# GPS.net
KiCad netlist of a schematic drawn in Altium Designer
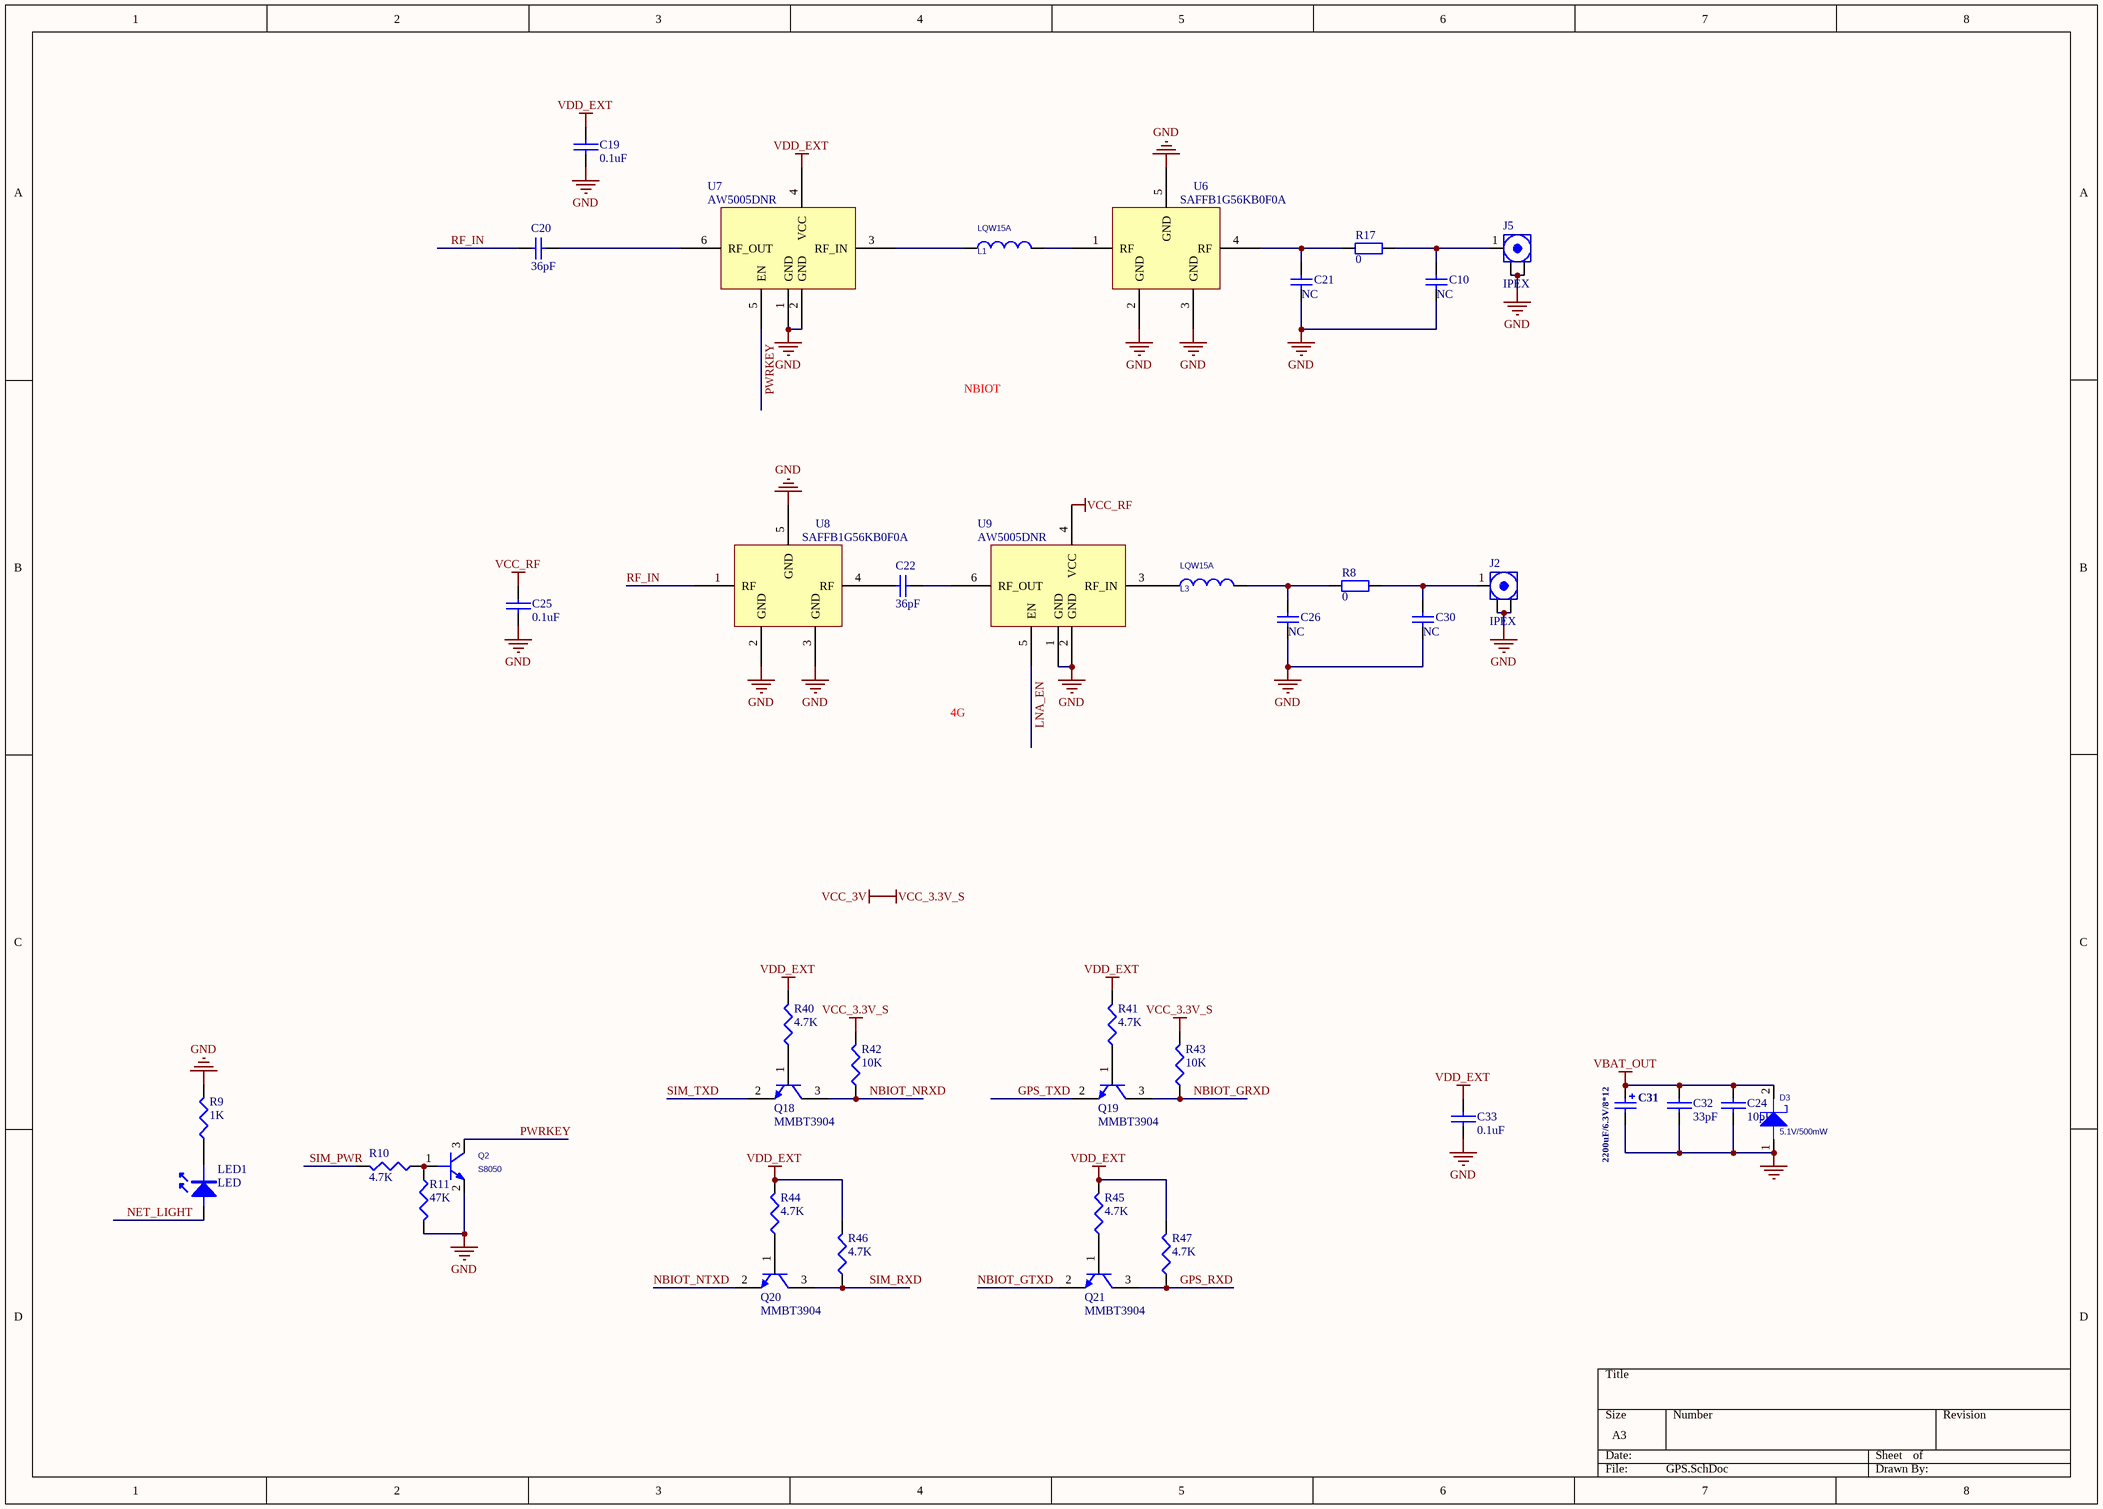
[diagram p0: GPS.SchDoc]

(export (version "E")
  (design (tool "Eeschema 10.0.6"))
  (components
    (comp (ref "C10")
      (value "NC")
      (footprint "0603C")
      (description "Capacitor")
      (fields (field (name "PUBLISHER") "Altium Limited"))
      (libsource (lib "Miscellaneous Devices") (part "Cap"))
    )
    (comp (ref "C19")
      (value "0.1uF")
      (footprint "0603C")
      (description "Capacitor")
      (libsource (lib "ZWLIntegrated_Library") (part "CAP"))
    )
    (comp (ref "C20")
      (value "36pF")
      (footprint "0603C")
      (description "Capacitor")
      (fields (field (name "PUBLISHER") "Altium Limited"))
      (libsource (lib "Miscellaneous Devices") (part "Cap"))
    )
    (comp (ref "C21")
      (value "NC")
      (footprint "0603C")
      (description "Capacitor")
      (fields (field (name "PUBLISHER") "Altium Limited"))
      (libsource (lib "Miscellaneous Devices") (part "Cap"))
    )
    (comp (ref "C22")
      (value "36pF")
      (footprint "0603C")
      (description "Capacitor")
      (fields (field (name "PUBLISHER") "Altium Limited"))
      (libsource (lib "Miscellaneous Devices") (part "Cap"))
    )
    (comp (ref "C24")
      (value "10pF")
      (footprint "0603C")
      (description "Capacitor")
      (libsource (lib "ZWLIntegrated_Library") (part "CAP"))
    )
    (comp (ref "C25")
      (value "0.1uF")
      (footprint "0603C")
      (description "Capacitor")
      (libsource (lib "ZWLIntegrated_Library") (part "CAP"))
    )
    (comp (ref "C26")
      (value "NC")
      (footprint "0603C")
      (description "Capacitor")
      (fields (field (name "PUBLISHER") "Altium Limited"))
      (libsource (lib "Miscellaneous Devices") (part "Cap"))
    )
    (comp (ref "C30")
      (value "NC")
      (footprint "0603C")
      (description "Capacitor")
      (fields (field (name "PUBLISHER") "Altium Limited"))
      (libsource (lib "Miscellaneous Devices") (part "Cap"))
    )
    (comp (ref "C31")
      (value "2200uF/6.3V/8*12")
      (footprint "8*12")
      (description "Polarized Capacitor (Surface Mount)")
      (libsource (lib "KT_iBeacon") (part "Cap Pol3"))
    )
    (comp (ref "C32")
      (value "33pF")
      (footprint "0603C")
      (description "Capacitor")
      (libsource (lib "ZWLIntegrated_Library") (part "CAP"))
    )
    (comp (ref "C33")
      (value "0.1uF")
      (footprint "0603C")
      (description "Capacitor")
      (libsource (lib "ZWLIntegrated_Library") (part "CAP"))
    )
    (comp (ref "D3")
      (value "5.1V/500mW")
      (footprint "LL-34(D1206)")
      (fields (field (name "Comment") "DIODE_SCHOTTKY_0"))
      (libsource (lib "KT_iBeacon") (part "DIODE_SCHOTTKY_0"))
    )
    (comp (ref "J2") (value "IPEX") (footprint "RF-UFL") (libsource (lib "我的元件库") (part "ANT")))
    (comp (ref "J5") (value "IPEX") (footprint "RF-UFL") (libsource (lib "我的元件库") (part "ANT")))
    (comp (ref "L1") (value "LQW15A") (footprint "0402R") (libsource (lib "*") (part "INDUCTOR_1")))
    (comp (ref "L3") (value "LQW15A") (footprint "0402R") (libsource (lib "*") (part "INDUCTOR_1")))
    (comp (ref "LED1") (value "LED") (footprint "0603LED") (libsource (lib "我的元件库") (part "LED")))
    (comp (ref "Q2") (value "S8050") (footprint "SOT23") (libsource (lib "*") (part "2N1069_1")))
    (comp (ref "Q18") (value "MMBT3904") (footprint "SOT23-3") (libsource (lib "Schlib1") (part "NPN")))
    (comp (ref "Q19") (value "MMBT3904") (footprint "SOT23-3") (libsource (lib "Schlib1") (part "NPN")))
    (comp (ref "Q20") (value "MMBT3904") (footprint "SOT23-3") (libsource (lib "Schlib1") (part "NPN")))
    (comp (ref "Q21") (value "MMBT3904") (footprint "SOT23-3") (libsource (lib "Schlib1") (part "NPN")))
    (comp (ref "R8")
      (value "0")
      (footprint "0603R")
      (description "Resistor")
      (fields (field (name "PUBLISHER") "Altium Limited"))
      (libsource (lib "Miscellaneous Devices") (part "Res2"))
    )
    (comp (ref "R9") (value "1K") (footprint "0603R") (libsource (lib "ZWLIntegrated_Library") (part "RES1")))
    (comp (ref "R10")
      (value "4.7K")
      (footprint "0603R")
      (libsource (lib "ZWLIntegrated_Library") (part "RES1"))
    )
    (comp (ref "R11")
      (value "47K")
      (footprint "0603R")
      (libsource (lib "ZWLIntegrated_Library") (part "RES1"))
    )
    (comp (ref "R17")
      (value "0")
      (footprint "0603R")
      (description "Resistor")
      (fields (field (name "PUBLISHER") "Altium Limited"))
      (libsource (lib "Miscellaneous Devices") (part "Res2"))
    )
    (comp (ref "R40")
      (value "4.7K")
      (footprint "0603R")
      (libsource (lib "ZWLIntegrated_Library") (part "RES1"))
    )
    (comp (ref "R41")
      (value "4.7K")
      (footprint "0603R")
      (libsource (lib "ZWLIntegrated_Library") (part "RES1"))
    )
    (comp (ref "R42")
      (value "10K")
      (footprint "0603R")
      (libsource (lib "ZWLIntegrated_Library") (part "RES1"))
    )
    (comp (ref "R43")
      (value "10K")
      (footprint "0603R")
      (libsource (lib "ZWLIntegrated_Library") (part "RES1"))
    )
    (comp (ref "R44")
      (value "4.7K")
      (footprint "0603R")
      (libsource (lib "ZWLIntegrated_Library") (part "RES1"))
    )
    (comp (ref "R45")
      (value "4.7K")
      (footprint "0603R")
      (libsource (lib "ZWLIntegrated_Library") (part "RES1"))
    )
    (comp (ref "R46")
      (value "4.7K")
      (footprint "0603R")
      (libsource (lib "ZWLIntegrated_Library") (part "RES1"))
    )
    (comp (ref "R47")
      (value "4.7K")
      (footprint "0603R")
      (libsource (lib "ZWLIntegrated_Library") (part "RES1"))
    )
    (comp (ref "U6")
      (value "SAFFB1G56KB0F0A")
      (footprint "SAFFB1G56KB0F0A")
      (libsource (lib "stm32") (part "SAFFB1G56KBOFA"))
    )
    (comp (ref "U7") (value "AW5005DNR") (libsource (lib "stm32") (part "AW5005DNR")))
    (comp (ref "U8")
      (value "SAFFB1G56KB0F0A")
      (footprint "SAFFB1G56KB0F0A")
      (libsource (lib "stm32") (part "SAFFB1G56KBOFA"))
    )
    (comp (ref "U9") (value "AW5005DNR") (libsource (lib "stm32") (part "AW5005DNR")))
  )
  (nets
    (net (code "1") (name "/GPS_RXD") (class "Default")
      (node (ref "Q21") (pin "3") (pinfunction "C_3") (pintype "passive"))
      (node (ref "R47") (pin "1") (pinfunction "1_1") (pintype "passive"))
    )
    (net (code "2") (name "/GPS_TXD") (class "Default")
      (node (ref "Q19") (pin "2") (pinfunction "E_2") (pintype "passive"))
    )
    (net (code "3") (name "/LNA_EN") (class "Default")
      (node (ref "U9") (pin "5") (pinfunction "EN_5") (pintype "passive"))
    )
    (net (code "4") (name "/NBIOT_GRXD") (class "Default")
      (node (ref "Q19") (pin "3") (pinfunction "C_3") (pintype "passive"))
      (node (ref "R43") (pin "1") (pinfunction "1_1") (pintype "passive"))
    )
    (net (code "5") (name "/NBIOT_GTXD") (class "Default")
      (node (ref "Q21") (pin "2") (pinfunction "E_2") (pintype "passive"))
    )
    (net (code "6") (name "/NBIOT_NRXD") (class "Default")
      (node (ref "Q18") (pin "3") (pinfunction "C_3") (pintype "passive"))
      (node (ref "R42") (pin "1") (pinfunction "1_1") (pintype "passive"))
    )
    (net (code "7") (name "/NBIOT_NTXD") (class "Default")
      (node (ref "Q20") (pin "2") (pinfunction "E_2") (pintype "passive"))
    )
    (net (code "8") (name "/NET_LIGHT") (class "Default")
      (node (ref "LED1") (pin "1") (pinfunction "1_1") (pintype "passive"))
    )
    (net (code "9") (name "/PWRKEY") (class "Default")
      (node (ref "Q2") (pin "3") (pinfunction "C_3") (pintype "passive"))
      (node (ref "U7") (pin "5") (pinfunction "EN_5") (pintype "passive"))
    )
    (net (code "10") (name "/RF_IN") (class "Default")
      (node (ref "C20") (pin "1") (pinfunction "1_1") (pintype "passive"))
      (node (ref "U8") (pin "1") (pinfunction "RF_1") (pintype "passive"))
    )
    (net (code "11") (name "/SIM_PWR") (class "Default")
      (node (ref "R10") (pin "2") (pinfunction "2_2") (pintype "passive"))
    )
    (net (code "12") (name "/SIM_RXD") (class "Default")
      (node (ref "Q20") (pin "3") (pinfunction "C_3") (pintype "passive"))
      (node (ref "R46") (pin "1") (pinfunction "1_1") (pintype "passive"))
    )
    (net (code "13") (name "/SIM_TXD") (class "Default")
      (node (ref "Q18") (pin "2") (pinfunction "E_2") (pintype "passive"))
    )
    (net (code "14") (name "GND") (class "Default")
      (node (ref "C10") (pin "2") (pinfunction "2_2") (pintype "passive"))
      (node (ref "C19") (pin "1") (pinfunction "1_1") (pintype "passive"))
      (node (ref "C21") (pin "2") (pinfunction "2_2") (pintype "passive"))
      (node (ref "C24") (pin "1") (pinfunction "1_1") (pintype "passive"))
      (node (ref "C25") (pin "1") (pinfunction "1_1") (pintype "passive"))
      (node (ref "C26") (pin "2") (pinfunction "2_2") (pintype "passive"))
      (node (ref "C30") (pin "2") (pinfunction "2_2") (pintype "passive"))
      (node (ref "C31") (pin "2") (pinfunction "2_2") (pintype "passive"))
      (node (ref "C32") (pin "1") (pinfunction "1_1") (pintype "passive"))
      (node (ref "C33") (pin "1") (pinfunction "1_1") (pintype "passive"))
      (node (ref "D3") (pin "1") (pinfunction "1_1") (pintype "passive"))
      (node (ref "J2") (pin "2") (pinfunction "Y_2") (pintype "passive"))
      (node (ref "J5") (pin "2") (pinfunction "Y_2") (pintype "passive"))
      (node (ref "Q2") (pin "2") (pinfunction "E_2") (pintype "passive"))
      (node (ref "R11") (pin "2") (pinfunction "2_2") (pintype "passive"))
      (node (ref "R9") (pin "2") (pinfunction "2_2") (pintype "passive"))
      (node (ref "U6") (pin "2") (pinfunction "GND_2") (pintype "passive"))
      (node (ref "U6") (pin "3") (pinfunction "GND_3") (pintype "passive"))
      (node (ref "U6") (pin "5") (pinfunction "GND_5") (pintype "passive"))
      (node (ref "U7") (pin "1") (pinfunction "GND_1") (pintype "passive"))
      (node (ref "U7") (pin "2") (pinfunction "GND_2") (pintype "passive"))
      (node (ref "U8") (pin "2") (pinfunction "GND_2") (pintype "passive"))
      (node (ref "U8") (pin "3") (pinfunction "GND_3") (pintype "passive"))
      (node (ref "U8") (pin "5") (pinfunction "GND_5") (pintype "passive"))
      (node (ref "U9") (pin "1") (pinfunction "GND_1") (pintype "passive"))
      (node (ref "U9") (pin "2") (pinfunction "GND_2") (pintype "passive"))
    )
    (net (code "15") (name "Net-(C21-Pad1)") (class "Default")
      (node (ref "C21") (pin "1") (pinfunction "1_1") (pintype "passive"))
      (node (ref "R17") (pin "1") (pinfunction "1_1") (pintype "passive"))
      (node (ref "U6") (pin "4") (pinfunction "RF_4") (pintype "passive"))
    )
    (net (code "16") (name "Net-(C22-Pad1)") (class "Default")
      (node (ref "C22") (pin "1") (pinfunction "1_1") (pintype "passive"))
      (node (ref "U8") (pin "4") (pinfunction "RF_4") (pintype "passive"))
    )
    (net (code "17") (name "Net-(C26-Pad1)") (class "Default")
      (node (ref "C26") (pin "1") (pinfunction "1_1") (pintype "passive"))
      (node (ref "L3") (pin "2") (pinfunction "2_2") (pintype "passive"))
      (node (ref "R8") (pin "1") (pinfunction "1_1") (pintype "passive"))
    )
    (net (code "18") (name "Net-(J2-X)") (class "Default")
      (node (ref "C30") (pin "1") (pinfunction "1_1") (pintype "passive"))
      (node (ref "J2") (pin "1") (pinfunction "X_1") (pintype "passive"))
      (node (ref "R8") (pin "2") (pinfunction "2_2") (pintype "passive"))
    )
    (net (code "19") (name "Net-(J5-X)") (class "Default")
      (node (ref "C10") (pin "1") (pinfunction "1_1") (pintype "passive"))
      (node (ref "J5") (pin "1") (pinfunction "X_1") (pintype "passive"))
      (node (ref "R17") (pin "2") (pinfunction "2_2") (pintype "passive"))
    )
    (net (code "20") (name "Net-(L1-Pad2)") (class "Default")
      (node (ref "L1") (pin "2") (pinfunction "2_2") (pintype "passive"))
      (node (ref "U6") (pin "1") (pinfunction "RF_1") (pintype "passive"))
    )
    (net (code "21") (name "Net-(LED1-Pad2)") (class "Default")
      (node (ref "LED1") (pin "2") (pinfunction "2_2") (pintype "passive"))
      (node (ref "R9") (pin "1") (pinfunction "1_1") (pintype "passive"))
    )
    (net (code "22") (name "Net-(Q2-B)") (class "Default")
      (node (ref "Q2") (pin "1") (pinfunction "B_1") (pintype "passive"))
      (node (ref "R10") (pin "1") (pinfunction "1_1") (pintype "passive"))
      (node (ref "R11") (pin "1") (pinfunction "1_1") (pintype "passive"))
    )
    (net (code "23") (name "Net-(Q18-B)") (class "Default")
      (node (ref "Q18") (pin "1") (pinfunction "B_1") (pintype "passive"))
      (node (ref "R40") (pin "1") (pinfunction "1_1") (pintype "passive"))
    )
    (net (code "24") (name "Net-(Q19-B)") (class "Default")
      (node (ref "Q19") (pin "1") (pinfunction "B_1") (pintype "passive"))
      (node (ref "R41") (pin "1") (pinfunction "1_1") (pintype "passive"))
    )
    (net (code "25") (name "Net-(Q20-B)") (class "Default")
      (node (ref "Q20") (pin "1") (pinfunction "B_1") (pintype "passive"))
      (node (ref "R44") (pin "1") (pinfunction "1_1") (pintype "passive"))
    )
    (net (code "26") (name "Net-(Q21-B)") (class "Default")
      (node (ref "Q21") (pin "1") (pinfunction "B_1") (pintype "passive"))
      (node (ref "R45") (pin "1") (pinfunction "1_1") (pintype "passive"))
    )
    (net (code "27") (name "Net-(U7-RF_IN)") (class "Default")
      (node (ref "L1") (pin "1") (pinfunction "1_1") (pintype "passive"))
      (node (ref "U7") (pin "3") (pinfunction "RF_IN_3") (pintype "passive"))
    )
    (net (code "28") (name "Net-(U7-RF_OUT)") (class "Default")
      (node (ref "C20") (pin "2") (pinfunction "2_2") (pintype "passive"))
      (node (ref "U7") (pin "6") (pinfunction "RF_OUT_6") (pintype "passive"))
    )
    (net (code "29") (name "Net-(U9-RF_IN)") (class "Default")
      (node (ref "L3") (pin "1") (pinfunction "1_1") (pintype "passive"))
      (node (ref "U9") (pin "3") (pinfunction "RF_IN_3") (pintype "passive"))
    )
    (net (code "30") (name "Net-(U9-RF_OUT)") (class "Default")
      (node (ref "C22") (pin "2") (pinfunction "2_2") (pintype "passive"))
      (node (ref "U9") (pin "6") (pinfunction "RF_OUT_6") (pintype "passive"))
    )
    (net (code "31") (name "VBAT_OUT") (class "Default")
      (node (ref "C24") (pin "2") (pinfunction "2_2") (pintype "passive"))
      (node (ref "C31") (pin "1") (pinfunction "1_1") (pintype "passive"))
      (node (ref "C32") (pin "2") (pinfunction "2_2") (pintype "passive"))
      (node (ref "D3") (pin "2") (pinfunction "2_2") (pintype "passive"))
    )
    (net (code "32") (name "VCC_3.3V_S") (class "Default")
      (node (ref "R42") (pin "2") (pinfunction "2_2") (pintype "passive"))
      (node (ref "R43") (pin "2") (pinfunction "2_2") (pintype "passive"))
    )
    (net (code "33") (name "VCC_RF") (class "Default")
      (node (ref "C25") (pin "2") (pinfunction "2_2") (pintype "passive"))
      (node (ref "U9") (pin "4") (pinfunction "VCC_4") (pintype "passive"))
    )
    (net (code "34") (name "VDD_EXT") (class "Default")
      (node (ref "C19") (pin "2") (pinfunction "2_2") (pintype "passive"))
      (node (ref "C33") (pin "2") (pinfunction "2_2") (pintype "passive"))
      (node (ref "R40") (pin "2") (pinfunction "2_2") (pintype "passive"))
      (node (ref "R41") (pin "2") (pinfunction "2_2") (pintype "passive"))
      (node (ref "R44") (pin "2") (pinfunction "2_2") (pintype "passive"))
      (node (ref "R45") (pin "2") (pinfunction "2_2") (pintype "passive"))
      (node (ref "R46") (pin "2") (pinfunction "2_2") (pintype "passive"))
      (node (ref "R47") (pin "2") (pinfunction "2_2") (pintype "passive"))
      (node (ref "U7") (pin "4") (pinfunction "VCC_4") (pintype "passive"))
    )
  )
)
